# Low_Distortion_Oscillator_Amp.net
KiCad netlist of a schematic drawn in Altium Designer
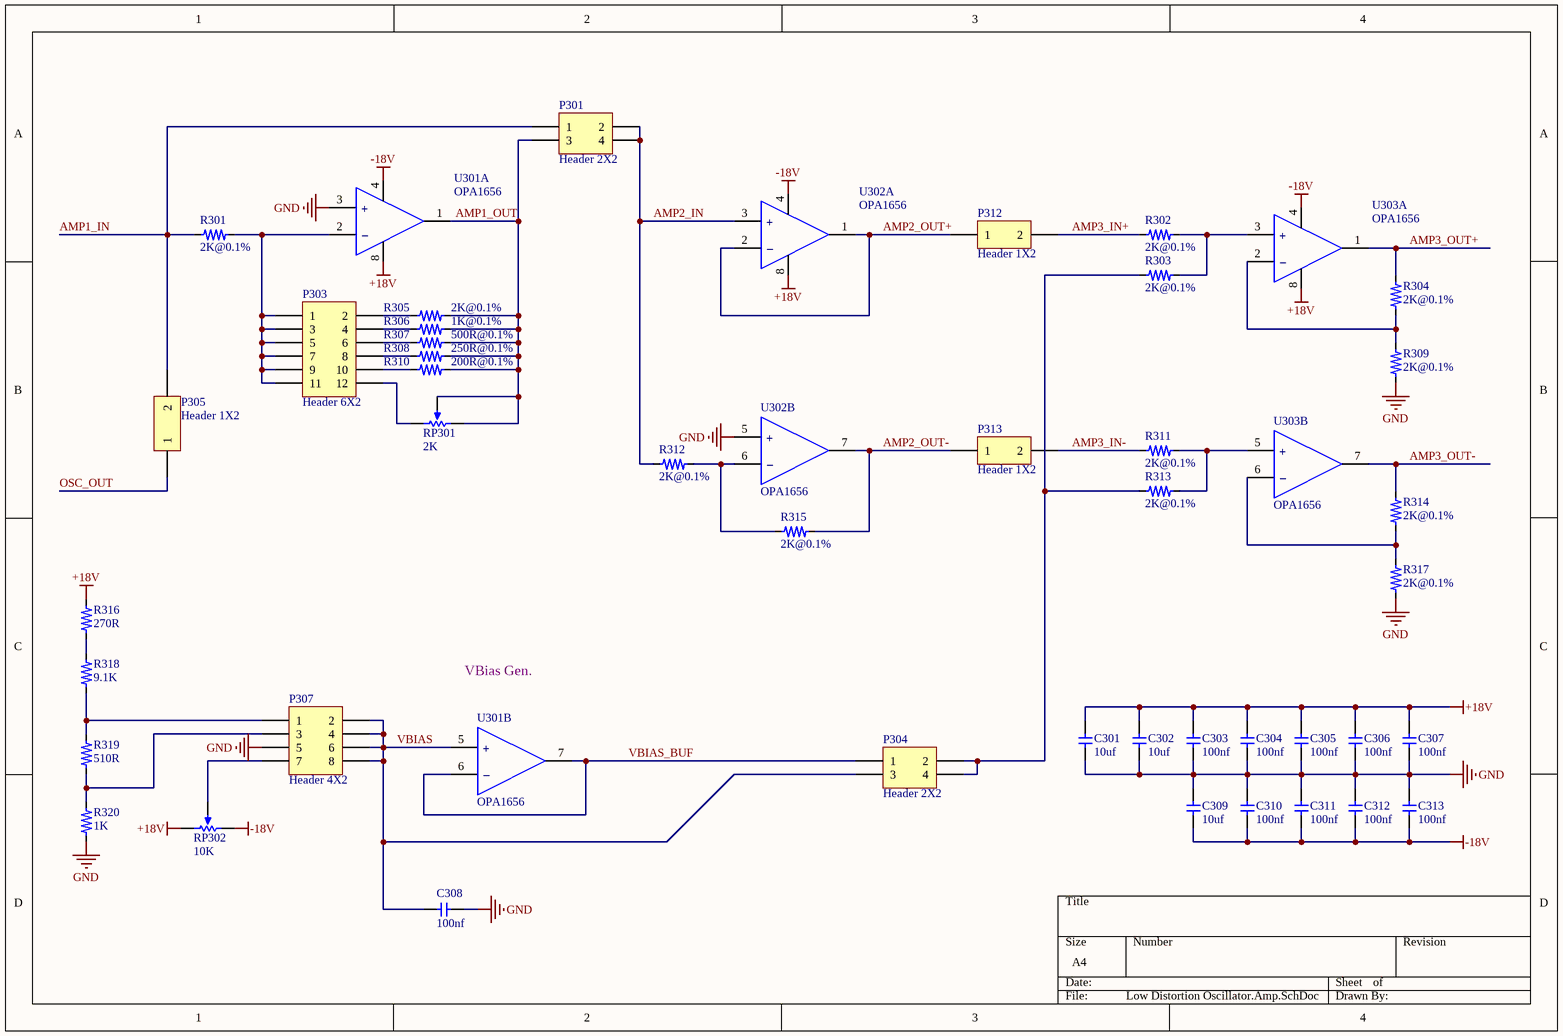
[diagram p0: Low Distortion Oscillator.Amp.SchDoc]

(export (version "E")
  (design (tool "Eeschema 10.0.6"))
  (components
    (comp (ref "C301")
      (value "10uf")
      (footprint "C1206")
      (fields (field (name "Comment") "Cap"))
      (libsource (lib "carrot_lib") (part "Cap"))
    )
    (comp (ref "C302")
      (value "10uf")
      (footprint "C1206")
      (fields (field (name "Comment") "Cap"))
      (libsource (lib "carrot_lib") (part "Cap"))
    )
    (comp (ref "C303")
      (value "100nf")
      (footprint "C0805")
      (fields (field (name "Comment") "Cap"))
      (libsource (lib "carrot_lib") (part "Cap"))
    )
    (comp (ref "C304")
      (value "100nf")
      (footprint "C0805")
      (fields (field (name "Comment") "Cap"))
      (libsource (lib "carrot_lib") (part "Cap"))
    )
    (comp (ref "C305")
      (value "100nf")
      (footprint "C0805")
      (fields (field (name "Comment") "Cap"))
      (libsource (lib "carrot_lib") (part "Cap"))
    )
    (comp (ref "C306")
      (value "100nf")
      (footprint "C0805")
      (fields (field (name "Comment") "Cap"))
      (libsource (lib "carrot_lib") (part "Cap"))
    )
    (comp (ref "C307")
      (value "100nf")
      (footprint "C0805")
      (fields (field (name "Comment") "Cap"))
      (libsource (lib "carrot_lib") (part "Cap"))
    )
    (comp (ref "C308")
      (value "100nf")
      (footprint "C0805")
      (fields (field (name "Comment") "Cap"))
      (libsource (lib "carrot_lib") (part "Cap"))
    )
    (comp (ref "C309")
      (value "10uf")
      (footprint "C1206")
      (fields (field (name "Comment") "Cap"))
      (libsource (lib "carrot_lib") (part "Cap"))
    )
    (comp (ref "C310")
      (value "100nf")
      (footprint "C0805")
      (fields (field (name "Comment") "Cap"))
      (libsource (lib "carrot_lib") (part "Cap"))
    )
    (comp (ref "C311")
      (value "100nf")
      (footprint "C0805")
      (fields (field (name "Comment") "Cap"))
      (libsource (lib "carrot_lib") (part "Cap"))
    )
    (comp (ref "C312")
      (value "100nf")
      (footprint "C0805")
      (fields (field (name "Comment") "Cap"))
      (libsource (lib "carrot_lib") (part "Cap"))
    )
    (comp (ref "C313")
      (value "100nf")
      (footprint "C0805")
      (fields (field (name "Comment") "Cap"))
      (libsource (lib "carrot_lib") (part "Cap"))
    )
    (comp (ref "P301")
      (value "Header 2X2")
      (footprint "HDR2X2")
      (description "Header, 2-Pin, Dual row")
      (libsource (lib "carrot_lib") (part "Header 2X2"))
    )
    (comp (ref "P303")
      (value "Header 6X2")
      (footprint "HDR2X6")
      (description "Header, 6-Pin, Dual row")
      (libsource (lib "carrot_lib") (part "Header 6X2"))
    )
    (comp (ref "P304")
      (value "Header 2X2")
      (footprint "HDR2X2")
      (description "Header, 2-Pin, Dual row")
      (libsource (lib "carrot_lib") (part "Header 2X2"))
    )
    (comp (ref "P305")
      (value "Header 1X2")
      (footprint "HDR2X1")
      (description "Header, 1-Pin, Dual row")
      (libsource (lib "") (part "Header 1X2_1"))
    )
    (comp (ref "P307")
      (value "Header 4X2")
      (footprint "HDR2X4")
      (description "Header, 4-Pin, Dual row")
      (libsource (lib "carrot_lib") (part "Header 4X2"))
    )
    (comp (ref "P312")
      (value "Header 1X2")
      (footprint "HDR2X1")
      (description "Header, 1-Pin, Dual row")
      (libsource (lib "carrot_lib") (part "Header 1X2"))
    )
    (comp (ref "P313")
      (value "Header 1X2")
      (footprint "HDR2X1")
      (description "Header, 1-Pin, Dual row")
      (libsource (lib "carrot_lib") (part "Header 1X2"))
    )
    (comp (ref "R301")
      (value "2K@0.1%")
      (footprint "R0805")
      (description "电阻")
      (fields (field (name "Comment") "Res"))
      (libsource (lib "carrot_lib") (part "Res"))
    )
    (comp (ref "R302")
      (value "2K@0.1%")
      (footprint "R0805")
      (description "电阻")
      (fields (field (name "Comment") "Res"))
      (libsource (lib "carrot_lib") (part "Res"))
    )
    (comp (ref "R303")
      (value "2K@0.1%")
      (footprint "R0805")
      (description "电阻")
      (fields (field (name "Comment") "Res"))
      (libsource (lib "carrot_lib") (part "Res"))
    )
    (comp (ref "R304")
      (value "2K@0.1%")
      (footprint "R0805")
      (description "电阻")
      (fields (field (name "Comment") "Res"))
      (libsource (lib "carrot_lib") (part "Res"))
    )
    (comp (ref "R305")
      (value "2K@0.1%")
      (footprint "R0805")
      (description "电阻")
      (fields (field (name "Comment") "Res"))
      (libsource (lib "carrot_lib") (part "Res"))
    )
    (comp (ref "R306")
      (value "1K@0.1%")
      (footprint "R0805")
      (description "电阻")
      (fields (field (name "Comment") "Res"))
      (libsource (lib "carrot_lib") (part "Res"))
    )
    (comp (ref "R307")
      (value "500R@0.1%")
      (footprint "R0805")
      (description "电阻")
      (fields (field (name "Comment") "Res"))
      (libsource (lib "carrot_lib") (part "Res"))
    )
    (comp (ref "R308")
      (value "250R@0.1%")
      (footprint "R0805")
      (description "电阻")
      (fields (field (name "Comment") "Res"))
      (libsource (lib "carrot_lib") (part "Res"))
    )
    (comp (ref "R309")
      (value "2K@0.1%")
      (footprint "R0805")
      (description "电阻")
      (fields (field (name "Comment") "Res"))
      (libsource (lib "carrot_lib") (part "Res"))
    )
    (comp (ref "R310")
      (value "200R@0.1%")
      (footprint "R0805")
      (description "电阻")
      (fields (field (name "Comment") "Res"))
      (libsource (lib "carrot_lib") (part "Res"))
    )
    (comp (ref "R311")
      (value "2K@0.1%")
      (footprint "R0805")
      (description "电阻")
      (fields (field (name "Comment") "Res"))
      (libsource (lib "carrot_lib") (part "Res"))
    )
    (comp (ref "R312")
      (value "2K@0.1%")
      (footprint "R0805")
      (description "电阻")
      (fields (field (name "Comment") "Res"))
      (libsource (lib "carrot_lib") (part "Res"))
    )
    (comp (ref "R313")
      (value "2K@0.1%")
      (footprint "R0805")
      (description "电阻")
      (fields (field (name "Comment") "Res"))
      (libsource (lib "carrot_lib") (part "Res"))
    )
    (comp (ref "R314")
      (value "2K@0.1%")
      (footprint "R0805")
      (description "电阻")
      (fields (field (name "Comment") "Res"))
      (libsource (lib "carrot_lib") (part "Res"))
    )
    (comp (ref "R315")
      (value "2K@0.1%")
      (footprint "R0805")
      (description "电阻")
      (fields (field (name "Comment") "Res"))
      (libsource (lib "carrot_lib") (part "Res"))
    )
    (comp (ref "R316")
      (value "270R")
      (footprint "R0805")
      (description "电阻")
      (fields (field (name "Comment") "Res"))
      (libsource (lib "carrot_lib") (part "Res"))
    )
    (comp (ref "R317")
      (value "2K@0.1%")
      (footprint "R0805")
      (description "电阻")
      (fields (field (name "Comment") "Res"))
      (libsource (lib "carrot_lib") (part "Res"))
    )
    (comp (ref "R318")
      (value "9.1K")
      (footprint "R0805")
      (description "电阻")
      (fields (field (name "Comment") "Res"))
      (libsource (lib "carrot_lib") (part "Res"))
    )
    (comp (ref "R319")
      (value "510R")
      (footprint "R0805")
      (description "电阻")
      (fields (field (name "Comment") "Res"))
      (libsource (lib "carrot_lib") (part "Res"))
    )
    (comp (ref "R320")
      (value "1K")
      (footprint "R0805")
      (description "电阻")
      (fields (field (name "Comment") "Res"))
      (libsource (lib "carrot_lib") (part "Res"))
    )
    (comp (ref "RP301")
      (value "2K")
      (footprint "RP-3590S-2")
      (description "电位器")
      (fields (field (name "Comment") "Res Pot"))
      (libsource (lib "carrot_lib") (part "Res Pot"))
    )
    (comp (ref "RP302")
      (value "10K")
      (footprint "RP-3590S-2")
      (description "电位器")
      (fields (field (name "Comment") "Res Pot"))
      (libsource (lib "carrot_lib") (part "Res Pot"))
    )
    (comp (ref "U301")
      (value "OPA1656")
      (footprint "OPAMP-SOIC8")
      (description "Universal Operational Amplifiers.")
      (libsource (lib "carrot_lib") (part "OP AMP 2#"))
    )
    (comp (ref "U302")
      (value "OPA1656")
      (footprint "OPAMP-SOIC8")
      (description "Universal Operational Amplifiers.")
      (libsource (lib "carrot_lib") (part "OP AMP 2#"))
    )
    (comp (ref "U303")
      (value "OPA1656")
      (footprint "OPAMP-SOIC8")
      (description "Universal Operational Amplifiers.")
      (libsource (lib "carrot_lib") (part "OP AMP 2#"))
    )
  )
  (nets
    (net (code "1") (name "+18V") (class "Default")
      (node (ref "C301") (pin "2") (pinfunction "2_2") (pintype "passive"))
      (node (ref "C302") (pin "2") (pinfunction "2_2") (pintype "passive"))
      (node (ref "C303") (pin "2") (pinfunction "2_2") (pintype "passive"))
      (node (ref "C304") (pin "2") (pinfunction "2_2") (pintype "passive"))
      (node (ref "C305") (pin "2") (pinfunction "2_2") (pintype "passive"))
      (node (ref "C306") (pin "2") (pinfunction "2_2") (pintype "passive"))
      (node (ref "C307") (pin "2") (pinfunction "2_2") (pintype "passive"))
      (node (ref "R316") (pin "2") (pinfunction "2_2") (pintype "passive"))
      (node (ref "RP302") (pin "3") (pinfunction "BOT_3") (pintype "passive"))
      (node (ref "U301") (pin "8") (pinfunction "+Vs_8") (pintype "passive"))
      (node (ref "U302") (pin "8") (pinfunction "+Vs_8") (pintype "passive"))
      (node (ref "U303") (pin "8") (pinfunction "+Vs_8") (pintype "passive"))
    )
    (net (code "2") (name "-18V") (class "Default")
      (node (ref "C309") (pin "1") (pinfunction "1_1") (pintype "passive"))
      (node (ref "C310") (pin "1") (pinfunction "1_1") (pintype "passive"))
      (node (ref "C311") (pin "1") (pinfunction "1_1") (pintype "passive"))
      (node (ref "C312") (pin "1") (pinfunction "1_1") (pintype "passive"))
      (node (ref "C313") (pin "1") (pinfunction "1_1") (pintype "passive"))
      (node (ref "RP302") (pin "1") (pinfunction "TOP_1") (pintype "passive"))
      (node (ref "U301") (pin "4") (pinfunction "-Vs_4") (pintype "passive"))
      (node (ref "U302") (pin "4") (pinfunction "-Vs_4") (pintype "passive"))
      (node (ref "U303") (pin "4") (pinfunction "-Vs_4") (pintype "passive"))
    )
    (net (code "3") (name "/AMP1_IN") (class "Default")
      (node (ref "P301") (pin "1") (pinfunction "1_1") (pintype "passive"))
      (node (ref "P305") (pin "2") (pinfunction "2_2") (pintype "passive"))
      (node (ref "R301") (pin "2") (pinfunction "2_2") (pintype "passive"))
    )
    (net (code "4") (name "/AMP1_OUT") (class "Default")
      (node (ref "P301") (pin "3") (pinfunction "3_3") (pintype "passive"))
      (node (ref "R305") (pin "1") (pinfunction "1_1") (pintype "passive"))
      (node (ref "R306") (pin "1") (pinfunction "1_1") (pintype "passive"))
      (node (ref "R307") (pin "1") (pinfunction "1_1") (pintype "passive"))
      (node (ref "R308") (pin "1") (pinfunction "1_1") (pintype "passive"))
      (node (ref "R310") (pin "1") (pinfunction "1_1") (pintype "passive"))
      (node (ref "RP301") (pin "1") (pinfunction "TOP_1") (pintype "passive"))
      (node (ref "RP301") (pin "2") (pinfunction "TAP_2") (pintype "passive"))
      (node (ref "U301") (pin "1") (pinfunction "OUT_A_1") (pintype "passive"))
    )
    (net (code "5") (name "/AMP2_IN") (class "Default")
      (node (ref "P301") (pin "2") (pinfunction "2_2") (pintype "passive"))
      (node (ref "P301") (pin "4") (pinfunction "4_4") (pintype "passive"))
      (node (ref "R312") (pin "2") (pinfunction "2_2") (pintype "passive"))
      (node (ref "U302") (pin "3") (pinfunction "+IN_A_3") (pintype "passive"))
    )
    (net (code "6") (name "/AMP2_OUT+") (class "Default")
      (node (ref "P312") (pin "1") (pinfunction "1_1") (pintype "passive"))
      (node (ref "U302") (pin "1") (pinfunction "OUT_A_1") (pintype "passive"))
      (node (ref "U302") (pin "2") (pinfunction "-IN_A_2") (pintype "passive"))
    )
    (net (code "7") (name "/AMP2_OUT-") (class "Default")
      (node (ref "P313") (pin "1") (pinfunction "1_1") (pintype "passive"))
      (node (ref "R315") (pin "1") (pinfunction "1_1") (pintype "passive"))
      (node (ref "U302") (pin "7") (pinfunction "OUT_B_7") (pintype "passive"))
    )
    (net (code "8") (name "/AMP3_IN+") (class "Default")
      (node (ref "P312") (pin "2") (pinfunction "2_2") (pintype "passive"))
      (node (ref "R302") (pin "2") (pinfunction "2_2") (pintype "passive"))
    )
    (net (code "9") (name "/AMP3_IN-") (class "Default")
      (node (ref "P313") (pin "2") (pinfunction "2_2") (pintype "passive"))
      (node (ref "R311") (pin "2") (pinfunction "2_2") (pintype "passive"))
    )
    (net (code "10") (name "/AMP3_OUT+") (class "Default")
      (node (ref "R304") (pin "1") (pinfunction "1_1") (pintype "passive"))
      (node (ref "U303") (pin "1") (pinfunction "OUT_A_1") (pintype "passive"))
    )
    (net (code "11") (name "/AMP3_OUT-") (class "Default")
      (node (ref "R314") (pin "1") (pinfunction "1_1") (pintype "passive"))
      (node (ref "U303") (pin "7") (pinfunction "OUT_B_7") (pintype "passive"))
    )
    (net (code "12") (name "/OSC_OUT") (class "Default")
      (node (ref "P305") (pin "1") (pinfunction "1_1") (pintype "passive"))
    )
    (net (code "13") (name "/VBIAS") (class "Default")
      (node (ref "C308") (pin "2") (pinfunction "2_2") (pintype "passive"))
      (node (ref "P304") (pin "3") (pinfunction "3_3") (pintype "passive"))
      (node (ref "P307") (pin "2") (pinfunction "2_2") (pintype "passive"))
      (node (ref "P307") (pin "4") (pinfunction "4_4") (pintype "passive"))
      (node (ref "P307") (pin "6") (pinfunction "6_6") (pintype "passive"))
      (node (ref "P307") (pin "8") (pinfunction "8_8") (pintype "passive"))
      (node (ref "U301") (pin "5") (pinfunction "+IN_B_5") (pintype "passive"))
    )
    (net (code "14") (name "/VBIAS_BUF") (class "Default")
      (node (ref "P304") (pin "1") (pinfunction "1_1") (pintype "passive"))
      (node (ref "U301") (pin "6") (pinfunction "-IN_B_6") (pintype "passive"))
      (node (ref "U301") (pin "7") (pinfunction "OUT_B_7") (pintype "passive"))
    )
    (net (code "15") (name "GND") (class "Default")
      (node (ref "C301") (pin "1") (pinfunction "1_1") (pintype "passive"))
      (node (ref "C302") (pin "1") (pinfunction "1_1") (pintype "passive"))
      (node (ref "C303") (pin "1") (pinfunction "1_1") (pintype "passive"))
      (node (ref "C304") (pin "1") (pinfunction "1_1") (pintype "passive"))
      (node (ref "C305") (pin "1") (pinfunction "1_1") (pintype "passive"))
      (node (ref "C306") (pin "1") (pinfunction "1_1") (pintype "passive"))
      (node (ref "C307") (pin "1") (pinfunction "1_1") (pintype "passive"))
      (node (ref "C308") (pin "1") (pinfunction "1_1") (pintype "passive"))
      (node (ref "C309") (pin "2") (pinfunction "2_2") (pintype "passive"))
      (node (ref "C310") (pin "2") (pinfunction "2_2") (pintype "passive"))
      (node (ref "C311") (pin "2") (pinfunction "2_2") (pintype "passive"))
      (node (ref "C312") (pin "2") (pinfunction "2_2") (pintype "passive"))
      (node (ref "C313") (pin "2") (pinfunction "2_2") (pintype "passive"))
      (node (ref "P307") (pin "5") (pinfunction "5_5") (pintype "passive"))
      (node (ref "R309") (pin "2") (pinfunction "2_2") (pintype "passive"))
      (node (ref "R317") (pin "2") (pinfunction "2_2") (pintype "passive"))
      (node (ref "R320") (pin "1") (pinfunction "1_1") (pintype "passive"))
      (node (ref "U301") (pin "3") (pinfunction "+IN_A_3") (pintype "passive"))
      (node (ref "U302") (pin "5") (pinfunction "+IN_B_5") (pintype "passive"))
    )
    (net (code "16") (name "Net-(P303-Pad2)") (class "Default")
      (node (ref "P303") (pin "2") (pinfunction "2_2") (pintype "passive"))
      (node (ref "R305") (pin "2") (pinfunction "2_2") (pintype "passive"))
    )
    (net (code "17") (name "Net-(P303-Pad4)") (class "Default")
      (node (ref "P303") (pin "4") (pinfunction "4_4") (pintype "passive"))
      (node (ref "R306") (pin "2") (pinfunction "2_2") (pintype "passive"))
    )
    (net (code "18") (name "Net-(P303-Pad6)") (class "Default")
      (node (ref "P303") (pin "6") (pinfunction "6_6") (pintype "passive"))
      (node (ref "R307") (pin "2") (pinfunction "2_2") (pintype "passive"))
    )
    (net (code "19") (name "Net-(P303-Pad8)") (class "Default")
      (node (ref "P303") (pin "8") (pinfunction "8_8") (pintype "passive"))
      (node (ref "R308") (pin "2") (pinfunction "2_2") (pintype "passive"))
    )
    (net (code "20") (name "Net-(P303-Pad10)") (class "Default")
      (node (ref "P303") (pin "10") (pinfunction "10_10") (pintype "passive"))
      (node (ref "R310") (pin "2") (pinfunction "2_2") (pintype "passive"))
    )
    (net (code "21") (name "Net-(P304-Pad2)") (class "Default")
      (node (ref "P304") (pin "2") (pinfunction "2_2") (pintype "passive"))
      (node (ref "P304") (pin "4") (pinfunction "4_4") (pintype "passive"))
      (node (ref "R303") (pin "2") (pinfunction "2_2") (pintype "passive"))
      (node (ref "R313") (pin "2") (pinfunction "2_2") (pintype "passive"))
    )
    (net (code "22") (name "Net-(P307-Pad1)") (class "Default")
      (node (ref "P307") (pin "1") (pinfunction "1_1") (pintype "passive"))
      (node (ref "R318") (pin "1") (pinfunction "1_1") (pintype "passive"))
      (node (ref "R319") (pin "2") (pinfunction "2_2") (pintype "passive"))
    )
    (net (code "23") (name "Net-(P307-Pad3)") (class "Default")
      (node (ref "P307") (pin "3") (pinfunction "3_3") (pintype "passive"))
      (node (ref "R319") (pin "1") (pinfunction "1_1") (pintype "passive"))
      (node (ref "R320") (pin "2") (pinfunction "2_2") (pintype "passive"))
    )
    (net (code "24") (name "Net-(R316-Pad1)") (class "Default")
      (node (ref "R316") (pin "1") (pinfunction "1_1") (pintype "passive"))
      (node (ref "R318") (pin "2") (pinfunction "2_2") (pintype "passive"))
    )
    (net (code "25") (name "Net-(RP301-BOT)") (class "Default")
      (node (ref "P303") (pin "12") (pinfunction "12_12") (pintype "passive"))
      (node (ref "RP301") (pin "3") (pinfunction "BOT_3") (pintype "passive"))
    )
    (net (code "26") (name "Net-(RP302-TAP)") (class "Default")
      (node (ref "P307") (pin "7") (pinfunction "7_7") (pintype "passive"))
      (node (ref "RP302") (pin "2") (pinfunction "TAP_2") (pintype "passive"))
    )
    (net (code "27") (name "Net-(U301A--IN_A)") (class "Default")
      (node (ref "P303") (pin "1") (pinfunction "1_1") (pintype "passive"))
      (node (ref "P303") (pin "11") (pinfunction "11_11") (pintype "passive"))
      (node (ref "P303") (pin "3") (pinfunction "3_3") (pintype "passive"))
      (node (ref "P303") (pin "5") (pinfunction "5_5") (pintype "passive"))
      (node (ref "P303") (pin "7") (pinfunction "7_7") (pintype "passive"))
      (node (ref "P303") (pin "9") (pinfunction "9_9") (pintype "passive"))
      (node (ref "R301") (pin "1") (pinfunction "1_1") (pintype "passive"))
      (node (ref "U301") (pin "2") (pinfunction "-IN_A_2") (pintype "passive"))
    )
    (net (code "28") (name "Net-(U302B--IN_B)") (class "Default")
      (node (ref "R312") (pin "1") (pinfunction "1_1") (pintype "passive"))
      (node (ref "R315") (pin "2") (pinfunction "2_2") (pintype "passive"))
      (node (ref "U302") (pin "6") (pinfunction "-IN_B_6") (pintype "passive"))
    )
    (net (code "29") (name "Net-(U303A-+IN_A)") (class "Default")
      (node (ref "R302") (pin "1") (pinfunction "1_1") (pintype "passive"))
      (node (ref "R303") (pin "1") (pinfunction "1_1") (pintype "passive"))
      (node (ref "U303") (pin "3") (pinfunction "+IN_A_3") (pintype "passive"))
    )
    (net (code "30") (name "Net-(U303A--IN_A)") (class "Default")
      (node (ref "R304") (pin "2") (pinfunction "2_2") (pintype "passive"))
      (node (ref "R309") (pin "1") (pinfunction "1_1") (pintype "passive"))
      (node (ref "U303") (pin "2") (pinfunction "-IN_A_2") (pintype "passive"))
    )
    (net (code "31") (name "Net-(U303B-+IN_B)") (class "Default")
      (node (ref "R311") (pin "1") (pinfunction "1_1") (pintype "passive"))
      (node (ref "R313") (pin "1") (pinfunction "1_1") (pintype "passive"))
      (node (ref "U303") (pin "5") (pinfunction "+IN_B_5") (pintype "passive"))
    )
    (net (code "32") (name "Net-(U303B--IN_B)") (class "Default")
      (node (ref "R314") (pin "2") (pinfunction "2_2") (pintype "passive"))
      (node (ref "R317") (pin "1") (pinfunction "1_1") (pintype "passive"))
      (node (ref "U303") (pin "6") (pinfunction "-IN_B_6") (pintype "passive"))
    )
  )
)
